# Sheet1.net
KiCad netlist of a schematic drawn in Altium Designer
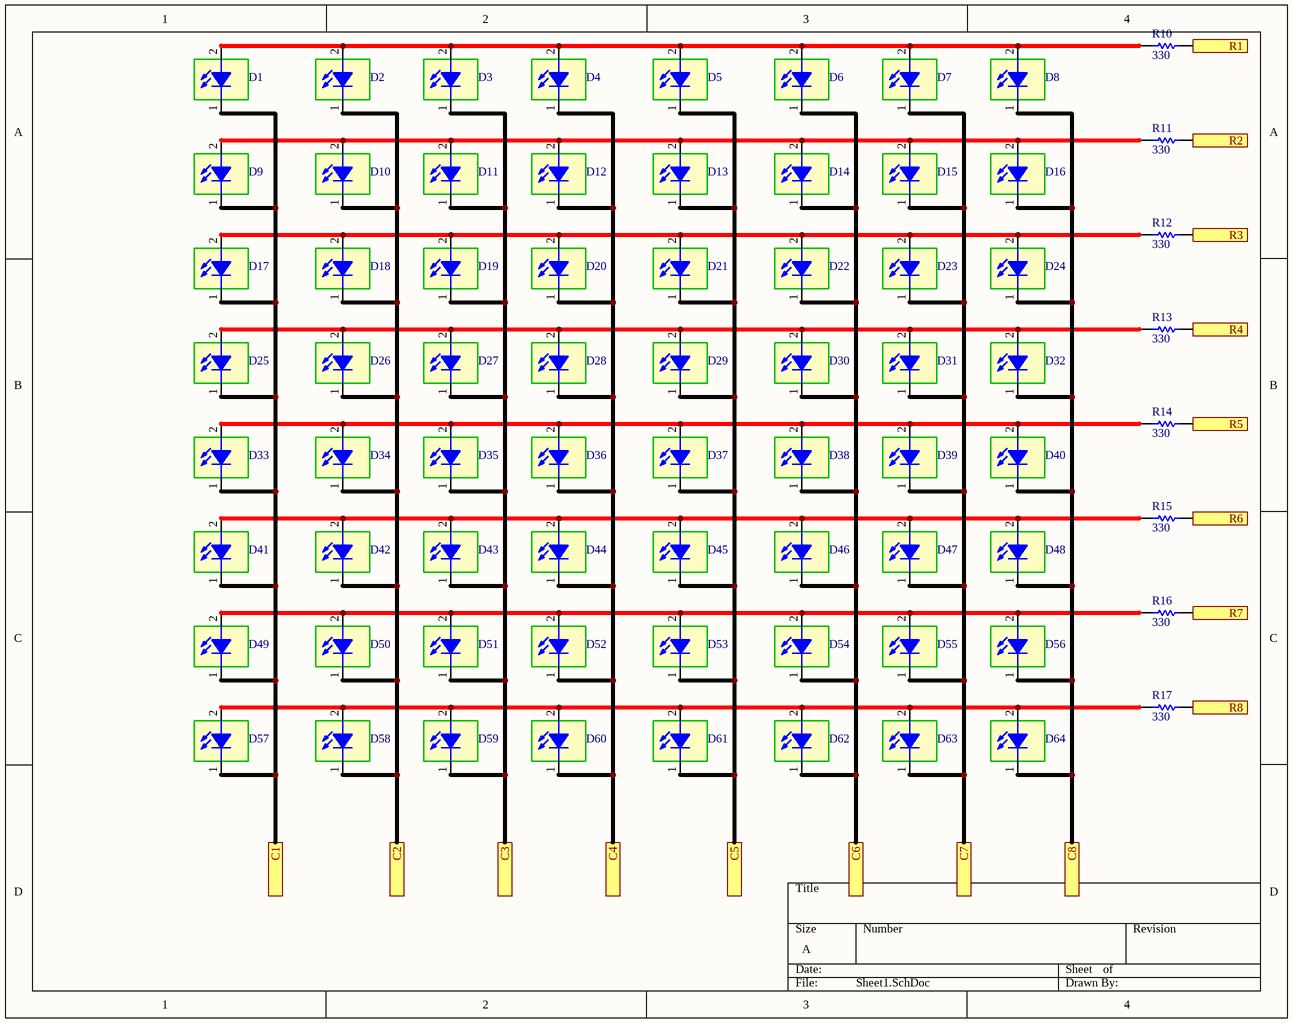
[diagram p0: Sheet1.SchDoc]

(export (version "E")
  (design (tool "Eeschema 10.0.6"))
  (components
    (comp (ref "D1")
      (value "SMD 1206 LED")
      (footprint "LED 1206")
      (libsource (lib "Altium") (part "LED SMD 1206"))
    )
    (comp (ref "D2")
      (value "SMD 1206 LED")
      (footprint "LED 1206")
      (libsource (lib "Altium") (part "LED SMD 1206"))
    )
    (comp (ref "D3")
      (value "SMD 1206 LED")
      (footprint "LED 1206")
      (libsource (lib "Altium") (part "LED SMD 1206"))
    )
    (comp (ref "D4")
      (value "SMD 1206 LED")
      (footprint "LED 1206")
      (libsource (lib "Altium") (part "LED SMD 1206"))
    )
    (comp (ref "D5")
      (value "SMD 1206 LED")
      (footprint "LED 1206")
      (libsource (lib "Altium") (part "LED SMD 1206"))
    )
    (comp (ref "D6")
      (value "SMD 1206 LED")
      (footprint "LED 1206")
      (libsource (lib "Altium") (part "LED SMD 1206"))
    )
    (comp (ref "D7")
      (value "SMD 1206 LED")
      (footprint "LED 1206")
      (libsource (lib "Altium") (part "LED SMD 1206"))
    )
    (comp (ref "D8")
      (value "SMD 1206 LED")
      (footprint "LED 1206")
      (libsource (lib "Altium") (part "LED SMD 1206"))
    )
    (comp (ref "D9")
      (value "SMD 1206 LED")
      (footprint "LED 1206")
      (libsource (lib "Altium") (part "LED SMD 1206"))
    )
    (comp (ref "D10")
      (value "SMD 1206 LED")
      (footprint "LED 1206")
      (libsource (lib "Altium") (part "LED SMD 1206"))
    )
    (comp (ref "D11")
      (value "SMD 1206 LED")
      (footprint "LED 1206")
      (libsource (lib "Altium") (part "LED SMD 1206"))
    )
    (comp (ref "D12")
      (value "SMD 1206 LED")
      (footprint "LED 1206")
      (libsource (lib "Altium") (part "LED SMD 1206"))
    )
    (comp (ref "D13")
      (value "SMD 1206 LED")
      (footprint "LED 1206")
      (libsource (lib "Altium") (part "LED SMD 1206"))
    )
    (comp (ref "D14")
      (value "SMD 1206 LED")
      (footprint "LED 1206")
      (libsource (lib "Altium") (part "LED SMD 1206"))
    )
    (comp (ref "D15")
      (value "SMD 1206 LED")
      (footprint "LED 1206")
      (libsource (lib "Altium") (part "LED SMD 1206"))
    )
    (comp (ref "D16")
      (value "SMD 1206 LED")
      (footprint "LED 1206")
      (libsource (lib "Altium") (part "LED SMD 1206"))
    )
    (comp (ref "D17")
      (value "SMD 1206 LED")
      (footprint "LED 1206")
      (libsource (lib "Altium") (part "LED SMD 1206"))
    )
    (comp (ref "D18")
      (value "SMD 1206 LED")
      (footprint "LED 1206")
      (libsource (lib "Altium") (part "LED SMD 1206"))
    )
    (comp (ref "D19")
      (value "SMD 1206 LED")
      (footprint "LED 1206")
      (libsource (lib "Altium") (part "LED SMD 1206"))
    )
    (comp (ref "D20")
      (value "SMD 1206 LED")
      (footprint "LED 1206")
      (libsource (lib "Altium") (part "LED SMD 1206"))
    )
    (comp (ref "D21")
      (value "SMD 1206 LED")
      (footprint "LED 1206")
      (libsource (lib "Altium") (part "LED SMD 1206"))
    )
    (comp (ref "D22")
      (value "SMD 1206 LED")
      (footprint "LED 1206")
      (libsource (lib "Altium") (part "LED SMD 1206"))
    )
    (comp (ref "D23")
      (value "SMD 1206 LED")
      (footprint "LED 1206")
      (libsource (lib "Altium") (part "LED SMD 1206"))
    )
    (comp (ref "D24")
      (value "SMD 1206 LED")
      (footprint "LED 1206")
      (libsource (lib "Altium") (part "LED SMD 1206"))
    )
    (comp (ref "D25")
      (value "SMD 1206 LED")
      (footprint "LED 1206")
      (libsource (lib "Altium") (part "LED SMD 1206"))
    )
    (comp (ref "D26")
      (value "SMD 1206 LED")
      (footprint "LED 1206")
      (libsource (lib "Altium") (part "LED SMD 1206"))
    )
    (comp (ref "D27")
      (value "SMD 1206 LED")
      (footprint "LED 1206")
      (libsource (lib "Altium") (part "LED SMD 1206"))
    )
    (comp (ref "D28")
      (value "SMD 1206 LED")
      (footprint "LED 1206")
      (libsource (lib "Altium") (part "LED SMD 1206"))
    )
    (comp (ref "D29")
      (value "SMD 1206 LED")
      (footprint "LED 1206")
      (libsource (lib "Altium") (part "LED SMD 1206"))
    )
    (comp (ref "D30")
      (value "SMD 1206 LED")
      (footprint "LED 1206")
      (libsource (lib "Altium") (part "LED SMD 1206"))
    )
    (comp (ref "D31")
      (value "SMD 1206 LED")
      (footprint "LED 1206")
      (libsource (lib "Altium") (part "LED SMD 1206"))
    )
    (comp (ref "D32")
      (value "SMD 1206 LED")
      (footprint "LED 1206")
      (libsource (lib "Altium") (part "LED SMD 1206"))
    )
    (comp (ref "D33")
      (value "SMD 1206 LED")
      (footprint "LED 1206")
      (libsource (lib "Altium") (part "LED SMD 1206"))
    )
    (comp (ref "D34")
      (value "SMD 1206 LED")
      (footprint "LED 1206")
      (libsource (lib "Altium") (part "LED SMD 1206"))
    )
    (comp (ref "D35")
      (value "SMD 1206 LED")
      (footprint "LED 1206")
      (libsource (lib "Altium") (part "LED SMD 1206"))
    )
    (comp (ref "D36")
      (value "SMD 1206 LED")
      (footprint "LED 1206")
      (libsource (lib "Altium") (part "LED SMD 1206"))
    )
    (comp (ref "D37")
      (value "SMD 1206 LED")
      (footprint "LED 1206")
      (libsource (lib "Altium") (part "LED SMD 1206"))
    )
    (comp (ref "D38")
      (value "SMD 1206 LED")
      (footprint "LED 1206")
      (libsource (lib "Altium") (part "LED SMD 1206"))
    )
    (comp (ref "D39")
      (value "SMD 1206 LED")
      (footprint "LED 1206")
      (libsource (lib "Altium") (part "LED SMD 1206"))
    )
    (comp (ref "D40")
      (value "SMD 1206 LED")
      (footprint "LED 1206")
      (libsource (lib "Altium") (part "LED SMD 1206"))
    )
    (comp (ref "D41")
      (value "SMD 1206 LED")
      (footprint "LED 1206")
      (libsource (lib "Altium") (part "LED SMD 1206"))
    )
    (comp (ref "D42")
      (value "SMD 1206 LED")
      (footprint "LED 1206")
      (libsource (lib "Altium") (part "LED SMD 1206"))
    )
    (comp (ref "D43")
      (value "SMD 1206 LED")
      (footprint "LED 1206")
      (libsource (lib "Altium") (part "LED SMD 1206"))
    )
    (comp (ref "D44")
      (value "SMD 1206 LED")
      (footprint "LED 1206")
      (libsource (lib "Altium") (part "LED SMD 1206"))
    )
    (comp (ref "D45")
      (value "SMD 1206 LED")
      (footprint "LED 1206")
      (libsource (lib "Altium") (part "LED SMD 1206"))
    )
    (comp (ref "D46")
      (value "SMD 1206 LED")
      (footprint "LED 1206")
      (libsource (lib "Altium") (part "LED SMD 1206"))
    )
    (comp (ref "D47")
      (value "SMD 1206 LED")
      (footprint "LED 1206")
      (libsource (lib "Altium") (part "LED SMD 1206"))
    )
    (comp (ref "D48")
      (value "SMD 1206 LED")
      (footprint "LED 1206")
      (libsource (lib "Altium") (part "LED SMD 1206"))
    )
    (comp (ref "D49")
      (value "SMD 1206 LED")
      (footprint "LED 1206")
      (libsource (lib "Altium") (part "LED SMD 1206"))
    )
    (comp (ref "D50")
      (value "SMD 1206 LED")
      (footprint "LED 1206")
      (libsource (lib "Altium") (part "LED SMD 1206"))
    )
    (comp (ref "D51")
      (value "SMD 1206 LED")
      (footprint "LED 1206")
      (libsource (lib "Altium") (part "LED SMD 1206"))
    )
    (comp (ref "D52")
      (value "SMD 1206 LED")
      (footprint "LED 1206")
      (libsource (lib "Altium") (part "LED SMD 1206"))
    )
    (comp (ref "D53")
      (value "SMD 1206 LED")
      (footprint "LED 1206")
      (libsource (lib "Altium") (part "LED SMD 1206"))
    )
    (comp (ref "D54")
      (value "SMD 1206 LED")
      (footprint "LED 1206")
      (libsource (lib "Altium") (part "LED SMD 1206"))
    )
    (comp (ref "D55")
      (value "SMD 1206 LED")
      (footprint "LED 1206")
      (libsource (lib "Altium") (part "LED SMD 1206"))
    )
    (comp (ref "D56")
      (value "SMD 1206 LED")
      (footprint "LED 1206")
      (libsource (lib "Altium") (part "LED SMD 1206"))
    )
    (comp (ref "D57")
      (value "SMD 1206 LED")
      (footprint "LED 1206")
      (libsource (lib "Altium") (part "LED SMD 1206"))
    )
    (comp (ref "D58")
      (value "SMD 1206 LED")
      (footprint "LED 1206")
      (libsource (lib "Altium") (part "LED SMD 1206"))
    )
    (comp (ref "D59")
      (value "SMD 1206 LED")
      (footprint "LED 1206")
      (libsource (lib "Altium") (part "LED SMD 1206"))
    )
    (comp (ref "D60")
      (value "SMD 1206 LED")
      (footprint "LED 1206")
      (libsource (lib "Altium") (part "LED SMD 1206"))
    )
    (comp (ref "D61")
      (value "SMD 1206 LED")
      (footprint "LED 1206")
      (libsource (lib "Altium") (part "LED SMD 1206"))
    )
    (comp (ref "D62")
      (value "SMD 1206 LED")
      (footprint "LED 1206")
      (libsource (lib "Altium") (part "LED SMD 1206"))
    )
    (comp (ref "D63")
      (value "SMD 1206 LED")
      (footprint "LED 1206")
      (libsource (lib "Altium") (part "LED SMD 1206"))
    )
    (comp (ref "D64")
      (value "SMD 1206 LED")
      (footprint "LED 1206")
      (libsource (lib "Altium") (part "LED SMD 1206"))
    )
    (comp (ref "R10")
      (value "330")
      (footprint "RES1206")
      (description "TOTAL SMD RESISTOR PACK")
      (fields (field (name "DESIGNER") "Abbas Basereh"))
      (libsource (lib "Altium") (part "RES SMD PACKAGE"))
    )
    (comp (ref "R11")
      (value "330")
      (footprint "RES1206")
      (description "TOTAL SMD RESISTOR PACK")
      (fields (field (name "DESIGNER") "Abbas Basereh"))
      (libsource (lib "Altium") (part "RES SMD PACKAGE"))
    )
    (comp (ref "R12")
      (value "330")
      (footprint "RES1206")
      (description "TOTAL SMD RESISTOR PACK")
      (fields (field (name "DESIGNER") "Abbas Basereh"))
      (libsource (lib "Altium") (part "RES SMD PACKAGE"))
    )
    (comp (ref "R13")
      (value "330")
      (footprint "RES1206")
      (description "TOTAL SMD RESISTOR PACK")
      (fields (field (name "DESIGNER") "Abbas Basereh"))
      (libsource (lib "Altium") (part "RES SMD PACKAGE"))
    )
    (comp (ref "R14")
      (value "330")
      (footprint "RES1206")
      (description "TOTAL SMD RESISTOR PACK")
      (fields (field (name "DESIGNER") "Abbas Basereh"))
      (libsource (lib "Altium") (part "RES SMD PACKAGE"))
    )
    (comp (ref "R15")
      (value "330")
      (footprint "RES1206")
      (description "TOTAL SMD RESISTOR PACK")
      (fields (field (name "DESIGNER") "Abbas Basereh"))
      (libsource (lib "Altium") (part "RES SMD PACKAGE"))
    )
    (comp (ref "R16")
      (value "330")
      (footprint "RES1206")
      (description "TOTAL SMD RESISTOR PACK")
      (fields (field (name "DESIGNER") "Abbas Basereh"))
      (libsource (lib "Altium") (part "RES SMD PACKAGE"))
    )
    (comp (ref "R17")
      (value "330")
      (footprint "RES1206")
      (description "TOTAL SMD RESISTOR PACK")
      (fields (field (name "DESIGNER") "Abbas Basereh"))
      (libsource (lib "Altium") (part "RES SMD PACKAGE"))
    )
  )
  (nets
    (net (code "1") (name "/C1") (class "Default")
      (node (ref "D1") (pin "1") (pinfunction "1_1") (pintype "passive"))
      (node (ref "D17") (pin "1") (pinfunction "1_1") (pintype "passive"))
      (node (ref "D25") (pin "1") (pinfunction "1_1") (pintype "passive"))
      (node (ref "D33") (pin "1") (pinfunction "1_1") (pintype "passive"))
      (node (ref "D41") (pin "1") (pinfunction "1_1") (pintype "passive"))
      (node (ref "D49") (pin "1") (pinfunction "1_1") (pintype "passive"))
      (node (ref "D57") (pin "1") (pinfunction "1_1") (pintype "passive"))
      (node (ref "D9") (pin "1") (pinfunction "1_1") (pintype "passive"))
    )
    (net (code "2") (name "/C2") (class "Default")
      (node (ref "D10") (pin "1") (pinfunction "1_1") (pintype "passive"))
      (node (ref "D18") (pin "1") (pinfunction "1_1") (pintype "passive"))
      (node (ref "D2") (pin "1") (pinfunction "1_1") (pintype "passive"))
      (node (ref "D26") (pin "1") (pinfunction "1_1") (pintype "passive"))
      (node (ref "D34") (pin "1") (pinfunction "1_1") (pintype "passive"))
      (node (ref "D42") (pin "1") (pinfunction "1_1") (pintype "passive"))
      (node (ref "D50") (pin "1") (pinfunction "1_1") (pintype "passive"))
      (node (ref "D58") (pin "1") (pinfunction "1_1") (pintype "passive"))
    )
    (net (code "3") (name "/C3") (class "Default")
      (node (ref "D11") (pin "1") (pinfunction "1_1") (pintype "passive"))
      (node (ref "D19") (pin "1") (pinfunction "1_1") (pintype "passive"))
      (node (ref "D27") (pin "1") (pinfunction "1_1") (pintype "passive"))
      (node (ref "D3") (pin "1") (pinfunction "1_1") (pintype "passive"))
      (node (ref "D35") (pin "1") (pinfunction "1_1") (pintype "passive"))
      (node (ref "D43") (pin "1") (pinfunction "1_1") (pintype "passive"))
      (node (ref "D51") (pin "1") (pinfunction "1_1") (pintype "passive"))
      (node (ref "D59") (pin "1") (pinfunction "1_1") (pintype "passive"))
    )
    (net (code "4") (name "/C4") (class "Default")
      (node (ref "D12") (pin "1") (pinfunction "1_1") (pintype "passive"))
      (node (ref "D20") (pin "1") (pinfunction "1_1") (pintype "passive"))
      (node (ref "D28") (pin "1") (pinfunction "1_1") (pintype "passive"))
      (node (ref "D36") (pin "1") (pinfunction "1_1") (pintype "passive"))
      (node (ref "D4") (pin "1") (pinfunction "1_1") (pintype "passive"))
      (node (ref "D44") (pin "1") (pinfunction "1_1") (pintype "passive"))
      (node (ref "D52") (pin "1") (pinfunction "1_1") (pintype "passive"))
      (node (ref "D60") (pin "1") (pinfunction "1_1") (pintype "passive"))
    )
    (net (code "5") (name "/C5") (class "Default")
      (node (ref "D13") (pin "1") (pinfunction "1_1") (pintype "passive"))
      (node (ref "D21") (pin "1") (pinfunction "1_1") (pintype "passive"))
      (node (ref "D29") (pin "1") (pinfunction "1_1") (pintype "passive"))
      (node (ref "D37") (pin "1") (pinfunction "1_1") (pintype "passive"))
      (node (ref "D45") (pin "1") (pinfunction "1_1") (pintype "passive"))
      (node (ref "D5") (pin "1") (pinfunction "1_1") (pintype "passive"))
      (node (ref "D53") (pin "1") (pinfunction "1_1") (pintype "passive"))
      (node (ref "D61") (pin "1") (pinfunction "1_1") (pintype "passive"))
    )
    (net (code "6") (name "/C6") (class "Default")
      (node (ref "D14") (pin "1") (pinfunction "1_1") (pintype "passive"))
      (node (ref "D22") (pin "1") (pinfunction "1_1") (pintype "passive"))
      (node (ref "D30") (pin "1") (pinfunction "1_1") (pintype "passive"))
      (node (ref "D38") (pin "1") (pinfunction "1_1") (pintype "passive"))
      (node (ref "D46") (pin "1") (pinfunction "1_1") (pintype "passive"))
      (node (ref "D54") (pin "1") (pinfunction "1_1") (pintype "passive"))
      (node (ref "D6") (pin "1") (pinfunction "1_1") (pintype "passive"))
      (node (ref "D62") (pin "1") (pinfunction "1_1") (pintype "passive"))
    )
    (net (code "7") (name "/C7") (class "Default")
      (node (ref "D15") (pin "1") (pinfunction "1_1") (pintype "passive"))
      (node (ref "D23") (pin "1") (pinfunction "1_1") (pintype "passive"))
      (node (ref "D31") (pin "1") (pinfunction "1_1") (pintype "passive"))
      (node (ref "D39") (pin "1") (pinfunction "1_1") (pintype "passive"))
      (node (ref "D47") (pin "1") (pinfunction "1_1") (pintype "passive"))
      (node (ref "D55") (pin "1") (pinfunction "1_1") (pintype "passive"))
      (node (ref "D63") (pin "1") (pinfunction "1_1") (pintype "passive"))
      (node (ref "D7") (pin "1") (pinfunction "1_1") (pintype "passive"))
    )
    (net (code "8") (name "/C8") (class "Default")
      (node (ref "D16") (pin "1") (pinfunction "1_1") (pintype "passive"))
      (node (ref "D24") (pin "1") (pinfunction "1_1") (pintype "passive"))
      (node (ref "D32") (pin "1") (pinfunction "1_1") (pintype "passive"))
      (node (ref "D40") (pin "1") (pinfunction "1_1") (pintype "passive"))
      (node (ref "D48") (pin "1") (pinfunction "1_1") (pintype "passive"))
      (node (ref "D56") (pin "1") (pinfunction "1_1") (pintype "passive"))
      (node (ref "D64") (pin "1") (pinfunction "1_1") (pintype "passive"))
      (node (ref "D8") (pin "1") (pinfunction "1_1") (pintype "passive"))
    )
    (net (code "9") (name "/R1") (class "Default")
      (node (ref "R10") (pin "1") (pinfunction "1_1") (pintype "passive"))
    )
    (net (code "10") (name "/R2") (class "Default")
      (node (ref "R11") (pin "1") (pinfunction "1_1") (pintype "passive"))
    )
    (net (code "11") (name "/R3") (class "Default")
      (node (ref "R12") (pin "1") (pinfunction "1_1") (pintype "passive"))
    )
    (net (code "12") (name "/R4") (class "Default")
      (node (ref "R13") (pin "1") (pinfunction "1_1") (pintype "passive"))
    )
    (net (code "13") (name "/R5") (class "Default")
      (node (ref "R14") (pin "1") (pinfunction "1_1") (pintype "passive"))
    )
    (net (code "14") (name "/R6") (class "Default")
      (node (ref "R15") (pin "1") (pinfunction "1_1") (pintype "passive"))
    )
    (net (code "15") (name "/R7") (class "Default")
      (node (ref "R16") (pin "1") (pinfunction "1_1") (pintype "passive"))
    )
    (net (code "16") (name "/R8") (class "Default")
      (node (ref "R17") (pin "1") (pinfunction "1_1") (pintype "passive"))
    )
    (net (code "17") (name "Net-(D1-Pad2)") (class "Default")
      (node (ref "D1") (pin "2") (pinfunction "2_2") (pintype "passive"))
      (node (ref "D2") (pin "2") (pinfunction "2_2") (pintype "passive"))
      (node (ref "D3") (pin "2") (pinfunction "2_2") (pintype "passive"))
      (node (ref "D4") (pin "2") (pinfunction "2_2") (pintype "passive"))
      (node (ref "D5") (pin "2") (pinfunction "2_2") (pintype "passive"))
      (node (ref "D6") (pin "2") (pinfunction "2_2") (pintype "passive"))
      (node (ref "D7") (pin "2") (pinfunction "2_2") (pintype "passive"))
      (node (ref "D8") (pin "2") (pinfunction "2_2") (pintype "passive"))
      (node (ref "R10") (pin "2") (pinfunction "2_2") (pintype "passive"))
    )
    (net (code "18") (name "Net-(D10-Pad2)") (class "Default")
      (node (ref "D10") (pin "2") (pinfunction "2_2") (pintype "passive"))
      (node (ref "D11") (pin "2") (pinfunction "2_2") (pintype "passive"))
      (node (ref "D12") (pin "2") (pinfunction "2_2") (pintype "passive"))
      (node (ref "D13") (pin "2") (pinfunction "2_2") (pintype "passive"))
      (node (ref "D14") (pin "2") (pinfunction "2_2") (pintype "passive"))
      (node (ref "D15") (pin "2") (pinfunction "2_2") (pintype "passive"))
      (node (ref "D16") (pin "2") (pinfunction "2_2") (pintype "passive"))
      (node (ref "D9") (pin "2") (pinfunction "2_2") (pintype "passive"))
      (node (ref "R11") (pin "2") (pinfunction "2_2") (pintype "passive"))
    )
    (net (code "19") (name "Net-(D17-Pad2)") (class "Default")
      (node (ref "D17") (pin "2") (pinfunction "2_2") (pintype "passive"))
      (node (ref "D18") (pin "2") (pinfunction "2_2") (pintype "passive"))
      (node (ref "D19") (pin "2") (pinfunction "2_2") (pintype "passive"))
      (node (ref "D20") (pin "2") (pinfunction "2_2") (pintype "passive"))
      (node (ref "D21") (pin "2") (pinfunction "2_2") (pintype "passive"))
      (node (ref "D22") (pin "2") (pinfunction "2_2") (pintype "passive"))
      (node (ref "D23") (pin "2") (pinfunction "2_2") (pintype "passive"))
      (node (ref "D24") (pin "2") (pinfunction "2_2") (pintype "passive"))
      (node (ref "R12") (pin "2") (pinfunction "2_2") (pintype "passive"))
    )
    (net (code "20") (name "Net-(D25-Pad2)") (class "Default")
      (node (ref "D25") (pin "2") (pinfunction "2_2") (pintype "passive"))
      (node (ref "D26") (pin "2") (pinfunction "2_2") (pintype "passive"))
      (node (ref "D27") (pin "2") (pinfunction "2_2") (pintype "passive"))
      (node (ref "D28") (pin "2") (pinfunction "2_2") (pintype "passive"))
      (node (ref "D29") (pin "2") (pinfunction "2_2") (pintype "passive"))
      (node (ref "D30") (pin "2") (pinfunction "2_2") (pintype "passive"))
      (node (ref "D31") (pin "2") (pinfunction "2_2") (pintype "passive"))
      (node (ref "D32") (pin "2") (pinfunction "2_2") (pintype "passive"))
      (node (ref "R13") (pin "2") (pinfunction "2_2") (pintype "passive"))
    )
    (net (code "21") (name "Net-(D33-Pad2)") (class "Default")
      (node (ref "D33") (pin "2") (pinfunction "2_2") (pintype "passive"))
      (node (ref "D34") (pin "2") (pinfunction "2_2") (pintype "passive"))
      (node (ref "D35") (pin "2") (pinfunction "2_2") (pintype "passive"))
      (node (ref "D36") (pin "2") (pinfunction "2_2") (pintype "passive"))
      (node (ref "D37") (pin "2") (pinfunction "2_2") (pintype "passive"))
      (node (ref "D38") (pin "2") (pinfunction "2_2") (pintype "passive"))
      (node (ref "D39") (pin "2") (pinfunction "2_2") (pintype "passive"))
      (node (ref "D40") (pin "2") (pinfunction "2_2") (pintype "passive"))
      (node (ref "R14") (pin "2") (pinfunction "2_2") (pintype "passive"))
    )
    (net (code "22") (name "Net-(D41-Pad2)") (class "Default")
      (node (ref "D41") (pin "2") (pinfunction "2_2") (pintype "passive"))
      (node (ref "D42") (pin "2") (pinfunction "2_2") (pintype "passive"))
      (node (ref "D43") (pin "2") (pinfunction "2_2") (pintype "passive"))
      (node (ref "D44") (pin "2") (pinfunction "2_2") (pintype "passive"))
      (node (ref "D45") (pin "2") (pinfunction "2_2") (pintype "passive"))
      (node (ref "D46") (pin "2") (pinfunction "2_2") (pintype "passive"))
      (node (ref "D47") (pin "2") (pinfunction "2_2") (pintype "passive"))
      (node (ref "D48") (pin "2") (pinfunction "2_2") (pintype "passive"))
      (node (ref "R15") (pin "2") (pinfunction "2_2") (pintype "passive"))
    )
    (net (code "23") (name "Net-(D49-Pad2)") (class "Default")
      (node (ref "D49") (pin "2") (pinfunction "2_2") (pintype "passive"))
      (node (ref "D50") (pin "2") (pinfunction "2_2") (pintype "passive"))
      (node (ref "D51") (pin "2") (pinfunction "2_2") (pintype "passive"))
      (node (ref "D52") (pin "2") (pinfunction "2_2") (pintype "passive"))
      (node (ref "D53") (pin "2") (pinfunction "2_2") (pintype "passive"))
      (node (ref "D54") (pin "2") (pinfunction "2_2") (pintype "passive"))
      (node (ref "D55") (pin "2") (pinfunction "2_2") (pintype "passive"))
      (node (ref "D56") (pin "2") (pinfunction "2_2") (pintype "passive"))
      (node (ref "R16") (pin "2") (pinfunction "2_2") (pintype "passive"))
    )
    (net (code "24") (name "Net-(D57-Pad2)") (class "Default")
      (node (ref "D57") (pin "2") (pinfunction "2_2") (pintype "passive"))
      (node (ref "D58") (pin "2") (pinfunction "2_2") (pintype "passive"))
      (node (ref "D59") (pin "2") (pinfunction "2_2") (pintype "passive"))
      (node (ref "D60") (pin "2") (pinfunction "2_2") (pintype "passive"))
      (node (ref "D61") (pin "2") (pinfunction "2_2") (pintype "passive"))
      (node (ref "D62") (pin "2") (pinfunction "2_2") (pintype "passive"))
      (node (ref "D63") (pin "2") (pinfunction "2_2") (pintype "passive"))
      (node (ref "D64") (pin "2") (pinfunction "2_2") (pintype "passive"))
      (node (ref "R17") (pin "2") (pinfunction "2_2") (pintype "passive"))
    )
  )
)
